# isoSPI-transformer.net
KiCad netlist of a schematic drawn in Altium Designer
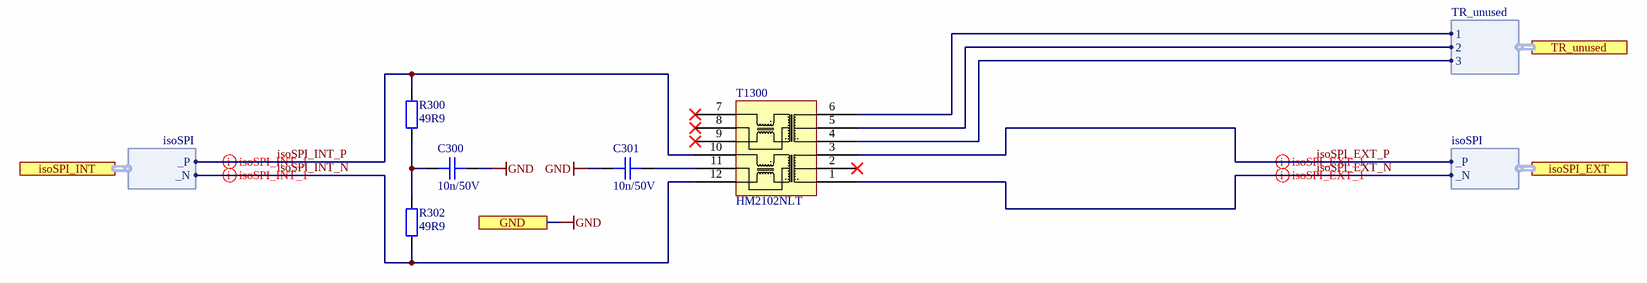
[diagram p0: isoSPI-transformer.SchDoc]

(export (version "E")
  (design (tool "Eeschema 10.0.6"))
  (components
    (comp (ref "C300")
      (value "10n/50V")
      (footprint "CAPC1608X08N")
      (description "MLCC")
      (fields (field (name "PART NUMBER") "gen_C_ceramic_10n_50V_C0G_0603"))
      (libsource (lib "OE750") (part "C"))
    )
    (comp (ref "C301")
      (value "10n/50V")
      (footprint "CAPC1608X08N")
      (description "MLCC")
      (fields (field (name "PART NUMBER") "gen_C_ceramic_10n_50V_C0G_0603"))
      (libsource (lib "OE750") (part "C"))
    )
    (comp (ref "R300")
      (value "49R9")
      (footprint "RESC1608X05N")
      (description "SMD Resistor 49R9 0603")
      (fields (field (name "PART NUMBER") "gen_R_49R9_0603") (field (name "TOLERANCE") "1%"))
      (libsource (lib "OE750") (part "R"))
    )
    (comp (ref "R302")
      (value "49R9")
      (footprint "RESC1608X05N")
      (description "SMD Resistor 49R9 0603")
      (fields (field (name "PART NUMBER") "gen_R_49R9_0603") (field (name "TOLERANCE") "1%"))
      (libsource (lib "OE750") (part "R"))
    )
    (comp (ref "T1300")
      (value "HM2102NLT")
      (footprint "HM2102NL")
      (description "Pulse HM2102NLT BMS Transformer")
      (fields (field (name "MANUFACTURER") "Pulse"))
      (libsource (lib "OE750") (part "HM2102NL"))
    )
  )
  (nets
    (net (code "3") (name "/1") (class "Default") (node (ref "T1300") (pin "6") (pintype "passive")))
    (net (code "4") (name "/2") (class "Default") (node (ref "T1300") (pin "5") (pintype "passive")))
    (net (code "5") (name "/3") (class "Default") (node (ref "T1300") (pin "4") (pintype "passive")))
    (net (code "6") (name "/isoSPI_EXT_N") (class "Default")
      (node (ref "T1300") (pin "1") (pintype "passive"))
    )
    (net (code "7") (name "/isoSPI_EXT_P") (class "Default")
      (node (ref "T1300") (pin "3") (pintype "passive"))
    )
    (net (code "8") (name "/isoSPI_INT_N") (class "Default")
      (node (ref "R302") (pin "1") (pinfunction "1_1") (pintype "passive"))
      (node (ref "T1300") (pin "12") (pintype "passive"))
    )
    (net (code "9") (name "/isoSPI_INT_P") (class "Default")
      (node (ref "R300") (pin "2") (pinfunction "2_2") (pintype "passive"))
      (node (ref "T1300") (pin "10") (pintype "passive"))
    )
    (net (code "12") (name "GND") (class "Default")
      (node (ref "C300") (pin "2") (pinfunction "2_2") (pintype "passive"))
      (node (ref "C301") (pin "1") (pinfunction "1_1") (pintype "passive"))
    )
    (net (code "13") (name "Net-(C300-Pad1)") (class "Default")
      (node (ref "C300") (pin "1") (pinfunction "1_1") (pintype "passive"))
      (node (ref "R300") (pin "1") (pinfunction "1_1") (pintype "passive"))
      (node (ref "R302") (pin "2") (pinfunction "2_2") (pintype "passive"))
    )
    (net (code "14") (name "Net-(C301-Pad2)") (class "Default")
      (node (ref "C301") (pin "2") (pinfunction "2_2") (pintype "passive"))
      (node (ref "T1300") (pin "11") (pintype "passive"))
    )
    (net (code "15") (name "unconnected-(T1300-Pad2)") (class "Default")
      (node (ref "T1300") (pin "2") (pintype "passive+no_connect"))
    )
    (net (code "16") (name "unconnected-(T1300-Pad7)") (class "Default")
      (node (ref "T1300") (pin "7") (pintype "passive+no_connect"))
    )
    (net (code "17") (name "unconnected-(T1300-Pad8)") (class "Default")
      (node (ref "T1300") (pin "8") (pintype "passive+no_connect"))
    )
    (net (code "18") (name "unconnected-(T1300-Pad9)") (class "Default")
      (node (ref "T1300") (pin "9") (pintype "passive+no_connect"))
    )
  )
)
